# button.net
KiCad netlist of a schematic drawn in Altium Designer
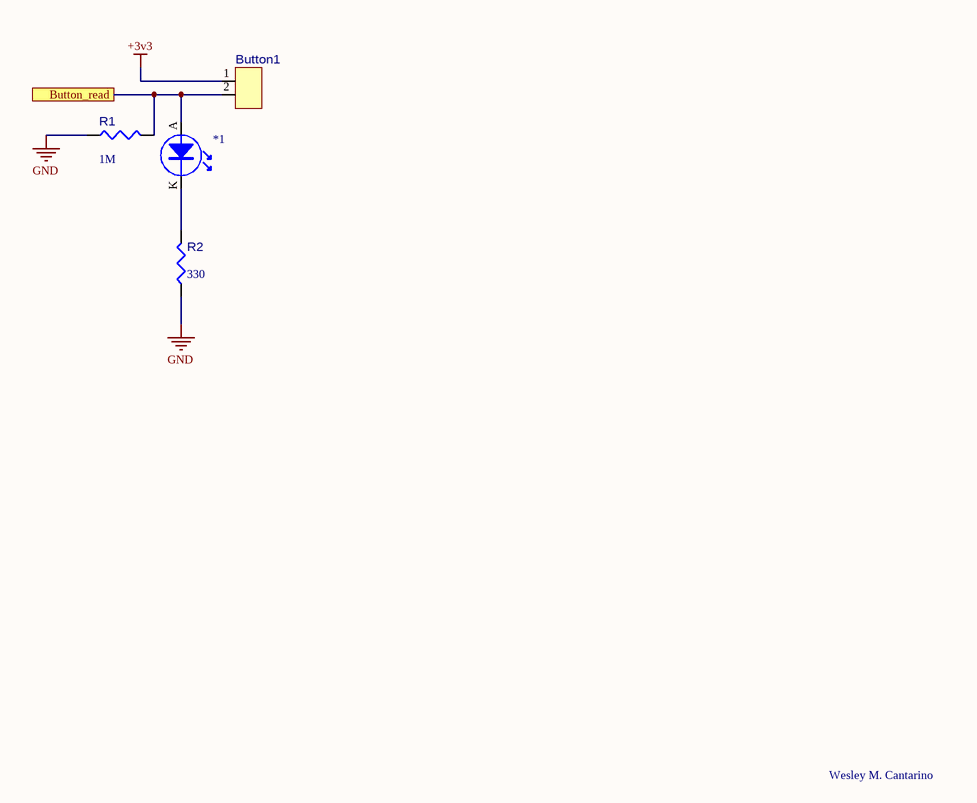
[diagram p0: button.SchDoc]

(export (version "E")
  (design (tool "Eeschema 10.0.6"))
  (components
    (comp (ref "*1")
      (value "LED_AXIAL_5MM")
      (footprint "HEADER_1X2")
      (libsource (lib "i9Library_Altium") (part "LED_AXIAL_5MM"))
    )
    (comp (ref "Button1")
      (value "?")
      (footprint "HEADER_1X2")
      (description "1X2")
      (libsource (lib "i9Library_Altium") (part "HEADER_1X2"))
    )
    (comp (ref "R1")
      (value "1M")
      (footprint "RES_PTH_7.62MM")
      (description "Pin Through Hole Resistor 7.62mm")
      (libsource (lib "i9Library_Altium") (part "RES_PTH_7.62MM"))
    )
    (comp (ref "R2")
      (value "330")
      (footprint "RES_PTH_7.62MM")
      (description "Pin Through Hole Resistor 7.62mm")
      (libsource (lib "i9Library_Altium") (part "RES_PTH_7.62MM"))
    )
  )
  (nets
    (net (code "1") (name "+3v3") (class "Default")
      (node (ref "Button1") (pin "1") (pinfunction "1_1") (pintype "passive"))
    )
    (net (code "2") (name "/Button_read") (class "Default")
      (node (ref "*1") (pin "A") (pintype "passive"))
      (node (ref "Button1") (pin "2") (pinfunction "2_2") (pintype "passive"))
      (node (ref "R1") (pin "2") (pinfunction "2_2") (pintype "passive"))
    )
    (net (code "3") (name "GND") (class "Default")
      (node (ref "R1") (pin "1") (pinfunction "1_1") (pintype "passive"))
      (node (ref "R2") (pin "1") (pinfunction "1_1") (pintype "passive"))
    )
    (net (code "4") (name "Net-(*1-PadK)") (class "Default")
      (node (ref "*1") (pin "K") (pintype "passive"))
      (node (ref "R2") (pin "2") (pinfunction "2_2") (pintype "passive"))
    )
  )
)
